# Sheet1.net
KiCad netlist of a schematic drawn in Altium Designer
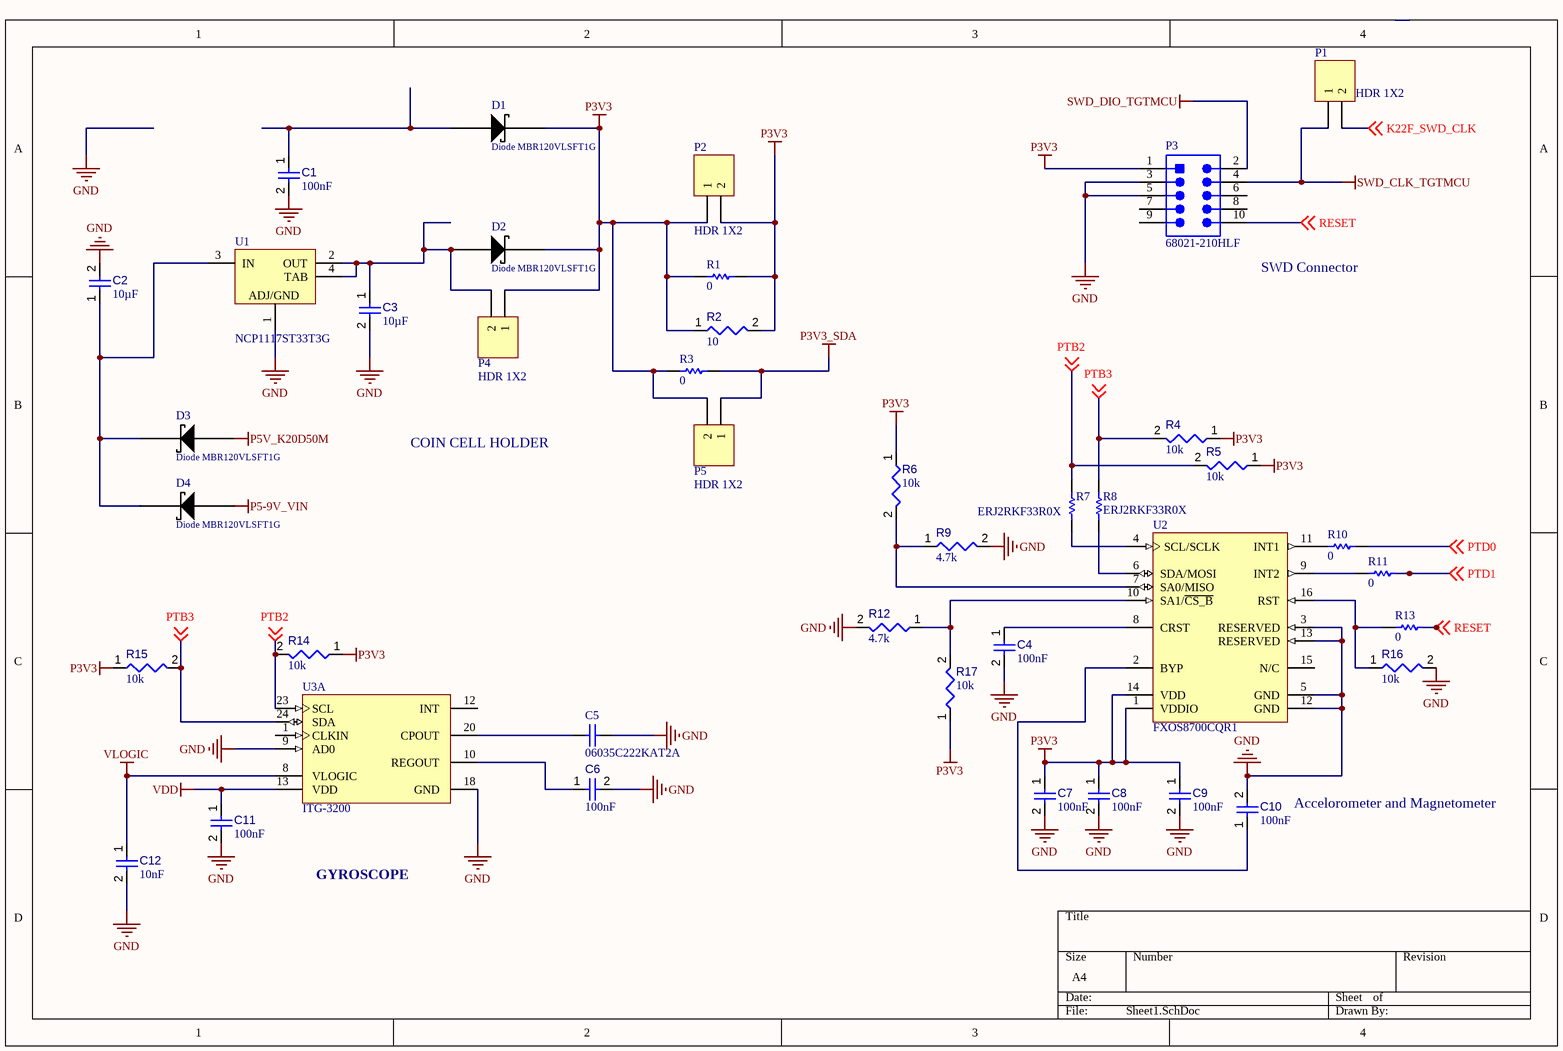
[diagram p0: Sheet1.SchDoc]

(export (version "E")
  (design (tool "Eeschema 10.0.6"))
  (components
    (comp (ref "C1")
      (value "100nF")
      (footprint "CAPC1608X90X40ML10T20")
      (description "Chip Capacitor, 100 nF, +/- 10%, 50 V, 0603 (1608 Metric)")
      (fields (field (name "TOLERANCE") "10%") (field (name "Comment") "Capacitor 100 nF +/-10% 50 V 0603"))
      (libsource (lib "James Cook University") (part "CAP-NP-2"))
    )
    (comp (ref "C2")
      (value "10µF")
      (footprint "CAPC0402(1005)60_L")
      (description "Chip Capacitor, 10µF +/-40%, 6.3V, 0402, Thickness 0.6 mm")
      (fields (field (name "TOLERANCE") "10%") (field (name "Comment") "Capacitor 10µF +/-40% 6.3V 0402"))
      (libsource (lib "James Cook University") (part "CAP-NP-2"))
    )
    (comp (ref "C3")
      (value "10µF")
      (footprint "CAPC0402(1005)60_L")
      (description "Chip Capacitor, 10µF +/-40%, 6.3V, 0402, Thickness 0.6 mm")
      (fields (field (name "TOLERANCE") "10%") (field (name "Comment") "Capacitor 10µF +/-40% 6.3V 0402"))
      (libsource (lib "James Cook University") (part "CAP-NP-2"))
    )
    (comp (ref "C4")
      (value "100nF")
      (footprint "CAPC1608X90X40ML10T20")
      (description "Chip Capacitor, 100 nF, +/- 10%, 50 V, 0603 (1608 Metric)")
      (fields (field (name "TOLERANCE") "10%") (field (name "Comment") "Capacitor 100 nF +/-10% 50 V 0603"))
      (libsource (lib "James Cook University") (part "CAP-NP-2"))
    )
    (comp (ref "C5")
      (value "06035C222KAT2A")
      (footprint "CAPC1608X90X35ML15T15")
      (fields (field (name "MANUFACTURER") "AVX Interconnect / Elco"))
      (libsource (lib "Altium Content Vault") (part "CAP"))
    )
    (comp (ref "C6")
      (value "100nF")
      (footprint "CAPC0402(1005)60_L")
      (description "Chip Capacitor, 100nF +/-20%, 50V, 0402, Thickness 0.6 mm")
      (fields (field (name "TOLERANCE") "10%") (field (name "Comment") "Capacitor 100nF +/-20% 50V 0402"))
      (libsource (lib "James Cook University") (part "CAP-NP-2"))
    )
    (comp (ref "C7")
      (value "100nF")
      (footprint "CAPC1608X90X40ML10T20")
      (description "Chip Capacitor, 100 nF, +/- 10%, 50 V, 0603 (1608 Metric)")
      (fields (field (name "TOLERANCE") "10%") (field (name "Comment") "Capacitor 100 nF +/-10% 50 V 0603"))
      (libsource (lib "James Cook University") (part "CAP-NP-2"))
    )
    (comp (ref "C8")
      (value "100nF")
      (footprint "CAPC1608X90X40ML10T20")
      (description "Chip Capacitor, 100 nF, +/- 10%, 50 V, 0603 (1608 Metric)")
      (fields (field (name "TOLERANCE") "10%") (field (name "Comment") "Capacitor 100 nF +/-10% 50 V 0603"))
      (libsource (lib "James Cook University") (part "CAP-NP-2"))
    )
    (comp (ref "C9")
      (value "100nF")
      (footprint "CAPC1608X90X40ML10T20")
      (description "Chip Capacitor, 100 nF, +/- 10%, 50 V, 0603 (1608 Metric)")
      (fields (field (name "TOLERANCE") "10%") (field (name "Comment") "Capacitor 100 nF +/-10% 50 V 0603"))
      (libsource (lib "James Cook University") (part "CAP-NP-2"))
    )
    (comp (ref "C10")
      (value "100nF")
      (footprint "CAPC1608X90X40ML10T20")
      (description "Chip Capacitor, 100 nF, +/- 10%, 50 V, 0603 (1608 Metric)")
      (fields (field (name "TOLERANCE") "10%") (field (name "Comment") "Capacitor 100 nF +/-10% 50 V 0603"))
      (libsource (lib "James Cook University") (part "CAP-NP-2"))
    )
    (comp (ref "C11")
      (value "100nF")
      (footprint "CAPC0402(1005)60_L")
      (description "Chip Capacitor, 100nF +/-20%, 50V, 0402, Thickness 0.6 mm")
      (fields (field (name "TOLERANCE") "10%") (field (name "Comment") "Capacitor 100nF +/-20% 50V 0402"))
      (libsource (lib "James Cook University") (part "CAP-NP-2"))
    )
    (comp (ref "C12")
      (value "10nF")
      (footprint "CAPC0402(1005)60_L")
      (description "Chip Capacitor, 10nF +/-20%, 50V, 0402, Thickness 0.6 mm")
      (fields (field (name "TOLERANCE") "5%") (field (name "Comment") "Capacitor 10nF +/-20% 50V 0402"))
      (libsource (lib "James Cook University") (part "CAP-NP-2"))
    )
    (comp (ref "D1")
      (value "Diode MBR120VLSFT1G")
      (footprint "SODFL360X100-2N")
      (description "MBR120VLSFT1G Schottky Rectifier, 20V, 1A")
      (fields (field (name "SOURCE") "JCULibrary.SchLib"))
      (libsource (lib "James Cook University") (part "Diode MBR120VLSFT1G"))
    )
    (comp (ref "D2")
      (value "Diode MBR120VLSFT1G")
      (footprint "SODFL360X100-2N")
      (description "MBR120VLSFT1G Schottky Rectifier, 20V, 1A")
      (fields (field (name "SOURCE") "JCULibrary.SchLib"))
      (libsource (lib "James Cook University") (part "Diode MBR120VLSFT1G"))
    )
    (comp (ref "D3")
      (value "Diode MBR120VLSFT1G")
      (footprint "SODFL360X100-2N")
      (description "MBR120VLSFT1G Schottky Rectifier, 20V, 1A")
      (fields (field (name "SOURCE") "JCULibrary.SchLib"))
      (libsource (lib "James Cook University") (part "Diode MBR120VLSFT1G"))
    )
    (comp (ref "D4")
      (value "Diode MBR120VLSFT1G")
      (footprint "SODFL360X100-2N")
      (description "MBR120VLSFT1G Schottky Rectifier, 20V, 1A")
      (fields (field (name "SOURCE") "JCULibrary.SchLib"))
      (libsource (lib "James Cook University") (part "Diode MBR120VLSFT1G"))
    )
    (comp (ref "P1")
      (value "HDR 1X2")
      (footprint "HDR1X2")
      (description "Header, 2-Pin")
      (fields (field (name "PUBLISHER") "Altium Limited"))
      (libsource (lib "") (part "Header 2_1"))
    )
    (comp (ref "P2")
      (value "HDR 1X2")
      (footprint "HDR1X2")
      (description "Header, 2-Pin")
      (fields (field (name "PUBLISHER") "Altium Limited"))
      (libsource (lib "") (part "Header 2_1"))
    )
    (comp (ref "P3")
      (value "68021-210HLF")
      (footprint "FCI-68021-210HLF-10_V")
      (description "Male Header, Pitch 2.54 mm, 2 x 5 Position, Height 4.83 mm, Tail Length 3.05 mm, Bulk")
      (fields (field (name "MANUFACTURER") "FCI Electronics"))
      (libsource (lib "James Cook University") (part "CN-2P-M-R10"))
    )
    (comp (ref "P4")
      (value "HDR 1X2")
      (footprint "HDR1X2")
      (description "Header, 2-Pin")
      (fields (field (name "PUBLISHER") "Altium Limited"))
      (libsource (lib "Miscellaneous Connectors") (part "Header 2"))
    )
    (comp (ref "P5")
      (value "HDR 1X2")
      (footprint "HDR1X2")
      (description "Header, 2-Pin")
      (fields (field (name "PUBLISHER") "Altium Limited"))
      (libsource (lib "Miscellaneous Connectors") (part "Header 2"))
    )
    (comp (ref "R1")
      (value "0")
      (footprint "RESC1005X40X25ML05T05")
      (description "Chip Resistor, 0 Ohm, 0.1 W, -55 to 155 degC, 0402 (1005 Metric)")
      (fields (field (name "TOLERANCE") "5%") (field (name "POWER") "100mW"))
      (libsource (lib "James Cook University") (part "RES-2"))
    )
    (comp (ref "R2")
      (value "10")
      (footprint "RESC0402(1005)_L")
      (description "Chip Resistor, 10 Ohms, +/-1 %, 63 mW, -55 to 155 degC, 0402")
      (fields (field (name "POWER") "63mW") (field (name "TOLERANCE") "1%"))
      (libsource (lib "") (part "RES-2_1"))
    )
    (comp (ref "R3")
      (value "0")
      (footprint "RESC1005X40X25ML05T05")
      (description "Chip Resistor, 0 Ohm, 0.1 W, -55 to 155 degC, 0402 (1005 Metric)")
      (fields (field (name "TOLERANCE") "5%") (field (name "POWER") "100mW"))
      (libsource (lib "James Cook University") (part "RES-2"))
    )
    (comp (ref "R4")
      (value "10k")
      (footprint "RESC1005X40X25ML05T05")
      (description "Chip Resistor, 10 KOhm, +/- 1%, 63 mW, -55 to 155 degC, 0402 (1005 Metric)")
      (fields (field (name "POWER") "63mW") (field (name "TOLERANCE") "1%"))
      (libsource (lib "") (part "RES-2_1"))
    )
    (comp (ref "R5")
      (value "10k")
      (footprint "RESC1005X40X25ML05T05")
      (description "Chip Resistor, 10 KOhm, +/- 1%, 63 mW, -55 to 155 degC, 0402 (1005 Metric)")
      (fields (field (name "POWER") "63mW") (field (name "TOLERANCE") "1%"))
      (libsource (lib "") (part "RES-2_1"))
    )
    (comp (ref "R6")
      (value "10k")
      (footprint "RESC1005X40X25ML05T05")
      (description "Chip Resistor, 10 KOhm, +/- 1%, 63 mW, -55 to 155 degC, 0402 (1005 Metric)")
      (fields (field (name "POWER") "63mW") (field (name "TOLERANCE") "1%"))
      (libsource (lib "") (part "RES-2_1"))
    )
    (comp (ref "R7")
      (value "ERJ2RKF33R0X")
      (footprint "RESC1005X40X25LL05T05")
      (fields (field (name "MANUFACTURER") "Panasonic"))
      (libsource (lib "Altium Content Vault") (part "RES"))
    )
    (comp (ref "R8")
      (value "ERJ2RKF33R0X")
      (footprint "RESC1005X40X25LL05T05")
      (fields (field (name "MANUFACTURER") "Panasonic"))
      (libsource (lib "Altium Content Vault") (part "RES"))
    )
    (comp (ref "R9")
      (value "4.7k")
      (footprint "RESC1608X55X25ML10T15")
      (description "Chip Resistor, 4.7 KOhm, +/- 1%, 0.1 W, -55 to 155 degC, 0603 (1608 Metric)")
      (fields (field (name "TOLERANCE") "1%") (field (name "POWER") "100mW"))
      (libsource (lib "") (part "RES-2_1"))
    )
    (comp (ref "R10")
      (value "0")
      (footprint "RESC1005X40X25ML05T05")
      (description "Chip Resistor, 0 Ohm, 0.1 W, -55 to 155 degC, 0402 (1005 Metric)")
      (fields (field (name "TOLERANCE") "5%") (field (name "POWER") "100mW"))
      (libsource (lib "James Cook University") (part "RES-2"))
    )
    (comp (ref "R11")
      (value "0")
      (footprint "RESC1005X40X25ML05T05")
      (description "Chip Resistor, 0 Ohm, 0.1 W, -55 to 155 degC, 0402 (1005 Metric)")
      (fields (field (name "TOLERANCE") "5%") (field (name "POWER") "100mW"))
      (libsource (lib "James Cook University") (part "RES-2"))
    )
    (comp (ref "R12")
      (value "4.7k")
      (footprint "RESC1608X55X25ML10T15")
      (description "Chip Resistor, 4.7 KOhm, +/- 1%, 0.1 W, -55 to 155 degC, 0603 (1608 Metric)")
      (fields (field (name "TOLERANCE") "1%") (field (name "POWER") "100mW"))
      (libsource (lib "") (part "RES-2_1"))
    )
    (comp (ref "R13")
      (value "0")
      (footprint "RESC1005X40X25ML05T05")
      (description "Chip Resistor, 0 Ohm, 0.1 W, -55 to 155 degC, 0402 (1005 Metric)")
      (fields (field (name "TOLERANCE") "5%") (field (name "POWER") "100mW"))
      (libsource (lib "James Cook University") (part "RES-2"))
    )
    (comp (ref "R14")
      (value "10k")
      (footprint "RESC1005X40X25ML05T05")
      (description "Chip Resistor, 10 KOhm, +/- 1%, 63 mW, -55 to 155 degC, 0402 (1005 Metric)")
      (fields (field (name "POWER") "63mW") (field (name "TOLERANCE") "1%"))
      (libsource (lib "") (part "RES-2_1"))
    )
    (comp (ref "R15")
      (value "10k")
      (footprint "RESC1005X40X25ML05T05")
      (description "Chip Resistor, 10 KOhm, +/- 1%, 63 mW, -55 to 155 degC, 0402 (1005 Metric)")
      (fields (field (name "POWER") "63mW") (field (name "TOLERANCE") "1%"))
      (libsource (lib "") (part "RES-2_1"))
    )
    (comp (ref "R16")
      (value "10k")
      (footprint "RESC1005X40X25ML05T05")
      (description "Chip Resistor, 10 KOhm, +/- 1%, 63 mW, -55 to 155 degC, 0402 (1005 Metric)")
      (fields (field (name "POWER") "63mW") (field (name "TOLERANCE") "1%"))
      (libsource (lib "") (part "RES-2_1"))
    )
    (comp (ref "R17")
      (value "10k")
      (footprint "RESC1005X40X25ML05T05")
      (description "Chip Resistor, 10 KOhm, +/- 1%, 63 mW, -55 to 155 degC, 0402 (1005 Metric)")
      (fields (field (name "POWER") "63mW") (field (name "TOLERANCE") "1%"))
      (libsource (lib "") (part "RES-2_1"))
    )
    (comp (ref "U1")
      (value "NCP1117ST33T3G")
      (footprint "ONSC-SOT-223-4-318H-01_A_V")
      (fields (field (name "MANUFACTURER") "ON Semiconductor"))
      (libsource (lib "James Cook University") (part "ONSC-NCP1117-SOT223-4"))
    )
    (comp (ref "U2")
      (value "FXOS8700CQR1")
      (footprint "FREE-QFN-16-3000X3000DE_V")
      (fields (field (name "MANUFACTURER") "Freescale"))
      (libsource (lib "Altium Content Vault") (part "FREE-FXOS8700CQR1-16"))
    )
    (comp (ref "U3")
      (value "ITG-3200")
      (footprint "INSE-QFN-24_A_M")
      (fields (field (name "MANUFACTURER") "InvenSense"))
      (libsource (lib "James Cook University") (part "INSE-ITG-3200-QFN-24"))
    )
  )
  (nets
    (net (code "1") (name "GND") (class "Default")
      (node (ref "C1") (pin "2") (pinfunction "2_2") (pintype "passive"))
      (node (ref "C10") (pin "2") (pinfunction "2_2") (pintype "passive"))
      (node (ref "C11") (pin "2") (pinfunction "2_2") (pintype "passive"))
      (node (ref "C12") (pin "2") (pinfunction "2_2") (pintype "passive"))
      (node (ref "C2") (pin "2") (pinfunction "2_2") (pintype "passive"))
      (node (ref "C3") (pin "2") (pinfunction "2_2") (pintype "passive"))
      (node (ref "C4") (pin "2") (pinfunction "2_2") (pintype "passive"))
      (node (ref "C5") (pin "2") (pinfunction "2_2") (pintype "passive"))
      (node (ref "C6") (pin "2") (pinfunction "2_2") (pintype "passive"))
      (node (ref "C7") (pin "2") (pinfunction "2_2") (pintype "passive"))
      (node (ref "C8") (pin "2") (pinfunction "2_2") (pintype "passive"))
      (node (ref "C9") (pin "2") (pinfunction "2_2") (pintype "passive"))
      (node (ref "P3") (pin "3") (pinfunction "3_3") (pintype "passive"))
      (node (ref "P3") (pin "5") (pinfunction "5_5") (pintype "passive"))
      (node (ref "R12") (pin "2") (pinfunction "2_2") (pintype "passive"))
      (node (ref "R16") (pin "2") (pinfunction "2_2") (pintype "passive"))
      (node (ref "R9") (pin "2") (pinfunction "2_2") (pintype "passive"))
      (node (ref "U1") (pin "1") (pinfunction "ADJ/GND_1") (pintype "passive"))
      (node (ref "U2") (pin "12") (pinfunction "GND_12") (pintype "power_in"))
      (node (ref "U2") (pin "13") (pinfunction "RESERVED_13") (pintype "input"))
      (node (ref "U2") (pin "3") (pinfunction "RESERVED_3") (pintype "input"))
      (node (ref "U2") (pin "5") (pinfunction "GND_5") (pintype "power_in"))
      (node (ref "U3") (pin "18") (pinfunction "GND_18") (pintype "power_in"))
      (node (ref "U3") (pin "9") (pinfunction "AD0_9") (pintype "input"))
    )
    (net (code "2") (name "K22F_SWD_CLK") (class "Default")
      (node (ref "P1") (pin "2") (pinfunction "2_2") (pintype "passive"))
    )
    (net (code "3") (name "Net-(C1-Pad1)") (class "Default")
      (node (ref "C1") (pin "1") (pinfunction "1_1") (pintype "passive"))
      (node (ref "D1") (pin "2") (pintype "passive"))
    )
    (net (code "4") (name "Net-(U1-IN)") (class "Default")
      (node (ref "C2") (pin "1") (pinfunction "1_1") (pintype "passive"))
      (node (ref "D3") (pin "1") (pintype "passive"))
      (node (ref "D4") (pin "1") (pintype "passive"))
      (node (ref "U1") (pin "3") (pinfunction "IN_3") (pintype "power_in"))
    )
    (net (code "5") (name "Net-(U1-OUT)") (class "Default")
      (node (ref "C3") (pin "1") (pinfunction "1_1") (pintype "passive"))
      (node (ref "D2") (pin "2") (pintype "passive"))
      (node (ref "P4") (pin "2") (pinfunction "2_2") (pintype "passive"))
      (node (ref "U1") (pin "2") (pinfunction "OUT_2") (pintype "power_in"))
      (node (ref "U1") (pin "4") (pinfunction "TAB_4") (pintype "passive"))
    )
    (net (code "6") (name "Net-(U2-BYP)") (class "Default")
      (node (ref "C10") (pin "1") (pinfunction "1_1") (pintype "passive"))
      (node (ref "U2") (pin "2") (pinfunction "BYP_2") (pintype "passive"))
    )
    (net (code "7") (name "Net-(U2-CRST)") (class "Default")
      (node (ref "C4") (pin "1") (pinfunction "1_1") (pintype "passive"))
      (node (ref "U2") (pin "8") (pinfunction "CRST_8") (pintype "passive"))
    )
    (net (code "8") (name "Net-(U2-INT1)") (class "Default")
      (node (ref "R10") (pin "1") (pinfunction "1_1") (pintype "passive"))
      (node (ref "U2") (pin "11") (pinfunction "INT1_11") (pintype "output"))
    )
    (net (code "9") (name "Net-(U2-INT2)") (class "Default")
      (node (ref "R11") (pin "1") (pinfunction "1_1") (pintype "passive"))
      (node (ref "U2") (pin "9") (pinfunction "INT2_9") (pintype "output"))
    )
    (net (code "10") (name "Net-(U2-RST)") (class "Default")
      (node (ref "R13") (pin "1") (pinfunction "1_1") (pintype "passive"))
      (node (ref "R16") (pin "1") (pinfunction "1_1") (pintype "passive"))
      (node (ref "U2") (pin "16") (pinfunction "RST_16") (pintype "input"))
    )
    (net (code "11") (name "Net-(U2-SA0{slash}MISO)") (class "Default")
      (node (ref "R6") (pin "2") (pinfunction "2_2") (pintype "passive"))
      (node (ref "R9") (pin "1") (pinfunction "1_1") (pintype "passive"))
      (node (ref "U2") (pin "7") (pinfunction "SA0/MISO_7") (pintype "bidirectional"))
    )
    (net (code "12") (name "Net-(U2-SA1{slash}~{CS_B})") (class "Default")
      (node (ref "R12") (pin "1") (pinfunction "1_1") (pintype "passive"))
      (node (ref "R17") (pin "2") (pinfunction "2_2") (pintype "passive"))
      (node (ref "U2") (pin "10") (pinfunction "SA1/~{CS_B}_10") (pintype "input"))
    )
    (net (code "13") (name "Net-(U2-SCL{slash}SCLK)") (class "Default")
      (node (ref "R7") (pin "1") (pinfunction "1_1") (pintype "passive"))
      (node (ref "U2") (pin "4") (pinfunction "SCL/SCLK_4") (pintype "input"))
    )
    (net (code "14") (name "Net-(U2-SDA{slash}MOSI)") (class "Default")
      (node (ref "R8") (pin "1") (pinfunction "1_1") (pintype "passive"))
      (node (ref "U2") (pin "6") (pinfunction "SDA/MOSI_6") (pintype "bidirectional"))
    )
    (net (code "15") (name "Net-(U3A-CPOUT)") (class "Default")
      (node (ref "C5") (pin "1") (pinfunction "1_1") (pintype "passive"))
      (node (ref "U3") (pin "20") (pinfunction "CPOUT_20") (pintype "passive"))
    )
    (net (code "16") (name "Net-(U3A-REGOUT)") (class "Default")
      (node (ref "C6") (pin "1") (pinfunction "1_1") (pintype "passive"))
      (node (ref "U3") (pin "10") (pinfunction "REGOUT_10") (pintype "passive"))
    )
    (net (code "17") (name "P3V3") (class "Default")
      (node (ref "C7") (pin "1") (pinfunction "1_1") (pintype "passive"))
      (node (ref "C8") (pin "1") (pinfunction "1_1") (pintype "passive"))
      (node (ref "C9") (pin "1") (pinfunction "1_1") (pintype "passive"))
      (node (ref "D1") (pin "1") (pintype "passive"))
      (node (ref "D2") (pin "1") (pintype "passive"))
      (node (ref "P2") (pin "1") (pinfunction "1_1") (pintype "passive"))
      (node (ref "P2") (pin "2") (pinfunction "2_2") (pintype "passive"))
      (node (ref "P3") (pin "1") (pinfunction "1_1") (pintype "passive"))
      (node (ref "P4") (pin "1") (pinfunction "1_1") (pintype "passive"))
      (node (ref "P5") (pin "2") (pinfunction "2_2") (pintype "passive"))
      (node (ref "R1") (pin "1") (pinfunction "1_1") (pintype "passive"))
      (node (ref "R1") (pin "2") (pinfunction "2_2") (pintype "passive"))
      (node (ref "R14") (pin "1") (pinfunction "1_1") (pintype "passive"))
      (node (ref "R15") (pin "1") (pinfunction "1_1") (pintype "passive"))
      (node (ref "R17") (pin "1") (pinfunction "1_1") (pintype "passive"))
      (node (ref "R2") (pin "1") (pinfunction "1_1") (pintype "passive"))
      (node (ref "R2") (pin "2") (pinfunction "2_2") (pintype "passive"))
      (node (ref "R3") (pin "1") (pinfunction "1_1") (pintype "passive"))
      (node (ref "R4") (pin "1") (pinfunction "1_1") (pintype "passive"))
      (node (ref "R5") (pin "1") (pinfunction "1_1") (pintype "passive"))
      (node (ref "R6") (pin "1") (pinfunction "1_1") (pintype "passive"))
      (node (ref "U2") (pin "1") (pinfunction "VDDIO_1") (pintype "power_in"))
      (node (ref "U2") (pin "14") (pinfunction "VDD_14") (pintype "power_in"))
    )
    (net (code "18") (name "P3V3_SDA") (class "Default")
      (node (ref "P5") (pin "1") (pinfunction "1_1") (pintype "passive"))
      (node (ref "R3") (pin "2") (pinfunction "2_2") (pintype "passive"))
    )
    (net (code "19") (name "P5-9V_VIN") (class "Default") (node (ref "D4") (pin "2") (pintype "passive")))
    (net (code "20") (name "P5V_K20D50M") (class "Default") (node (ref "D3") (pin "2") (pintype "passive")))
    (net (code "21") (name "PTB2") (class "Default")
      (node (ref "R14") (pin "2") (pinfunction "2_2") (pintype "passive"))
      (node (ref "R5") (pin "2") (pinfunction "2_2") (pintype "passive"))
      (node (ref "R7") (pin "2") (pinfunction "2_2") (pintype "passive"))
      (node (ref "U3") (pin "23") (pinfunction "SCL_23") (pintype "input"))
    )
    (net (code "22") (name "PTB3") (class "Default")
      (node (ref "R15") (pin "2") (pinfunction "2_2") (pintype "passive"))
      (node (ref "R4") (pin "2") (pinfunction "2_2") (pintype "passive"))
      (node (ref "R8") (pin "2") (pinfunction "2_2") (pintype "passive"))
      (node (ref "U3") (pin "24") (pinfunction "SDA_24") (pintype "bidirectional"))
    )
    (net (code "23") (name "PTD0") (class "Default")
      (node (ref "R10") (pin "2") (pinfunction "2_2") (pintype "passive"))
    )
    (net (code "24") (name "PTD1") (class "Default")
      (node (ref "R11") (pin "2") (pinfunction "2_2") (pintype "passive"))
    )
    (net (code "25") (name "RESET") (class "Default")
      (node (ref "P3") (pin "10") (pinfunction "10_10") (pintype "passive"))
      (node (ref "R13") (pin "2") (pinfunction "2_2") (pintype "passive"))
    )
    (net (code "26") (name "SWD_CLK_TGTMCU") (class "Default")
      (node (ref "P1") (pin "1") (pinfunction "1_1") (pintype "passive"))
      (node (ref "P3") (pin "4") (pinfunction "4_4") (pintype "passive"))
    )
    (net (code "27") (name "SWD_DIO_TGTMCU") (class "Default")
      (node (ref "P3") (pin "2") (pinfunction "2_2") (pintype "passive"))
    )
    (net (code "28") (name "VDD") (class "Default")
      (node (ref "C11") (pin "1") (pinfunction "1_1") (pintype "passive"))
      (node (ref "U3") (pin "13") (pinfunction "VDD_13") (pintype "power_in"))
    )
    (net (code "29") (name "VLOGIC") (class "Default")
      (node (ref "C12") (pin "1") (pinfunction "1_1") (pintype "passive"))
      (node (ref "U3") (pin "8") (pinfunction "VLOGIC_8") (pintype "power_in"))
    )
    (net (code "30") (name "unconnected-(P3-Pad6)") (class "Default")
      (node (ref "P3") (pin "6") (pinfunction "6_6") (pintype "passive"))
    )
    (net (code "31") (name "unconnected-(P3-Pad7)") (class "Default")
      (node (ref "P3") (pin "7") (pinfunction "7_7") (pintype "passive"))
    )
    (net (code "32") (name "unconnected-(P3-Pad8)") (class "Default")
      (node (ref "P3") (pin "8") (pinfunction "8_8") (pintype "passive"))
    )
    (net (code "33") (name "unconnected-(P3-Pad9)") (class "Default")
      (node (ref "P3") (pin "9") (pinfunction "9_9") (pintype "passive"))
    )
    (net (code "34") (name "unconnected-(U2-N{slash}C-Pad15)") (class "Default")
      (node (ref "U2") (pin "15") (pinfunction "N/C_15") (pintype "passive"))
    )
    (net (code "35") (name "unconnected-(U3A-CLKIN-Pad1)") (class "Default")
      (node (ref "U3") (pin "1") (pinfunction "CLKIN_1") (pintype "input"))
    )
    (net (code "36") (name "unconnected-(U3A-INT-Pad12)") (class "Default")
      (node (ref "U3") (pin "12") (pinfunction "INT_12") (pintype "open_collector"))
    )
  )
)
